# microphone_adapter_top.net
KiCad netlist of a schematic drawn in Altium Designer
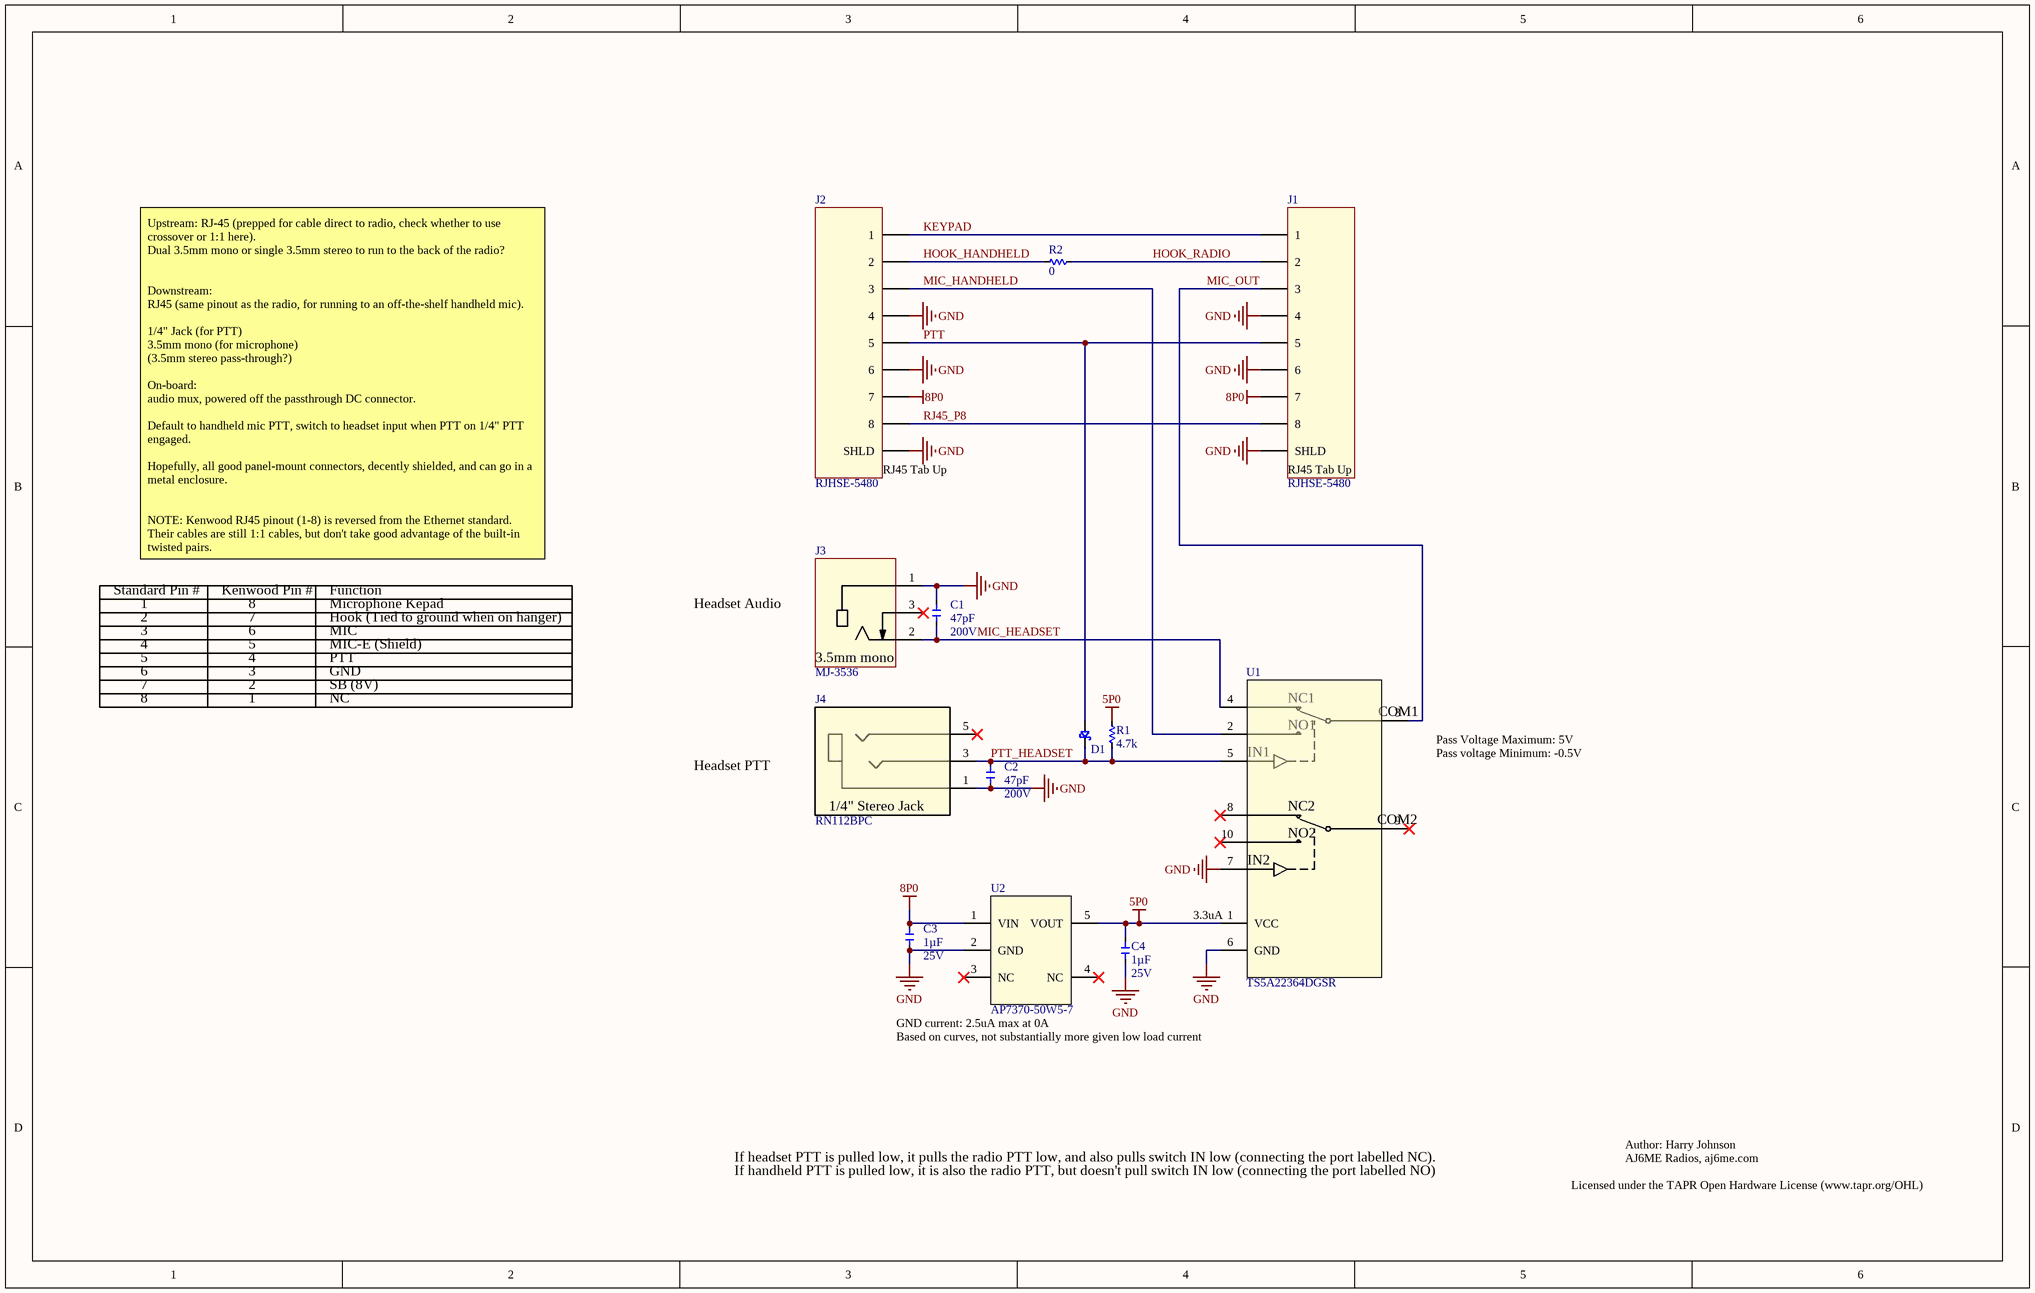
[diagram p0: microphone_adapter_top.SchDoc]

(export (version "E")
  (design (tool "Eeschema 10.0.6"))
  (components
    (comp (ref "C1")
      (value "GRM21A5C2D470JW01D")
      (footprint "C0805_1.30MM")
      (description "CAP CER 47PF 200V C0G/NP0 0805")
      (fields
        (field (name "CAPACITANCE") "47pF")
        (field (name "VOLTAGE - RATED") "200V")
        (field (name "DIGI-KEY PART NUMBER") "490-14653-1-ND")
        (field (name "MANUFACTURER") "Murata Electronics")
      )
      (libsource (lib "passives") (part "2pin_nonpolar_capacitor"))
    )
    (comp (ref "C2")
      (value "GRM21A5C2D470JW01D")
      (footprint "C0805_1.30MM")
      (description "CAP CER 47PF 200V C0G/NP0 0805")
      (fields
        (field (name "CAPACITANCE") "47pF")
        (field (name "VOLTAGE - RATED") "200V")
        (field (name "DIGI-KEY PART NUMBER") "490-14653-1-ND")
        (field (name "MANUFACTURER") "Murata Electronics")
      )
      (libsource (lib "passives") (part "2pin_nonpolar_capacitor"))
    )
    (comp (ref "C3")
      (value "GRM155C81E105ME11D")
      (footprint "C0402_0.55MM")
      (description "CAP CER 1UF 25V X6S 0402")
      (fields
        (field (name "CAPACITANCE") "1µF")
        (field (name "VOLTAGE - RATED") "25V")
        (field (name "DIGI-KEY PART NUMBER") "490-10015-1-ND")
        (field (name "MANUFACTURER") "Murata Electronics")
      )
      (libsource (lib "passives") (part "2pin_nonpolar_capacitor"))
    )
    (comp (ref "C4")
      (value "GRM155C81E105ME11D")
      (footprint "C0402_0.55MM")
      (description "CAP CER 1UF 25V X6S 0402")
      (fields
        (field (name "CAPACITANCE") "1µF")
        (field (name "VOLTAGE - RATED") "25V")
        (field (name "DIGI-KEY PART NUMBER") "490-10015-1-ND")
        (field (name "MANUFACTURER") "Murata Electronics")
      )
      (libsource (lib "passives") (part "2pin_nonpolar_capacitor"))
    )
    (comp (ref "D1")
      (value "BAT54XV2T1G")
      (footprint "SOD523_ONSEMI")
      (description "ON Semi BAT54XV2T1G; SMT Schottky Diode; 30V 200mA; 5ns; 2-Pin SOD-523")
      (fields (field (name "MANUFACTURER") "ON Semiconductor"))
      (libsource (lib "library") (part "DIODE_SCHOTTKY_30V_100MA_BAT54XV2T1G"))
    )
    (comp (ref "J1")
      (value "RJHSE-5480")
      (footprint "ETH_RJ45_RA_RJHSE-5480")
      (description "Conn RJ-45 F 8 POS 2.03mm Solder RA Thru-Hole 8 Terminal 1 Port Tray Cat 5")
      (fields (field (name "MANUFACTURER") "Amphenol"))
      (libsource (lib "library") (part "CONN_ETH_RJ45_RA_SHLD_RJHSE-5480_ALT"))
    )
    (comp (ref "J2")
      (value "RJHSE-5480")
      (footprint "ETH_RJ45_RA_RJHSE-5480")
      (description "Conn RJ-45 F 8 POS 2.03mm Solder RA Thru-Hole 8 Terminal 1 Port Tray Cat 5")
      (fields (field (name "MANUFACTURER") "Amphenol"))
      (libsource (lib "") (part "CONN_ETH_RJ45_RA_SHLD_RJHSE-5480_ALT_1"))
    )
    (comp (ref "J3")
      (value "MJ-3536")
      (footprint "AUD_CUI_MJ-3536")
      (description "CONN JACK MONO 3.5MM R/A")
      (fields (field (name "MANUFACTURER") "CUI"))
      (libsource (lib "library") (part "CONN_AUD_3.5_MM_MONO_MJ-3536"))
    )
    (comp (ref "J4")
      (value "RN112BPC")
      (footprint "AUD_SWITCHCRAFT_RN112BPC")
      (description "CONN JACK STEREO 0.25\" (6.35MM) R/A")
      (fields (field (name "MANUFACTURER") "Switchcraft"))
      (libsource (lib "library") (part "CONN_AUD_250_MIL_RN112BPC"))
    )
    (comp (ref "R1")
      (value "RC0402FR-074K7L")
      (footprint "R0402_0.40MM")
      (description "RES SMD 4.7K OHM 1% 1/16W 0402")
      (fields
        (field (name "RESISTANCE") "4.7k")
        (field (name "DIGI-KEY PART NUMBER") "311-4.7KLRCT-ND")
        (field (name "MANUFACTURER") "Yageo")
      )
      (libsource (lib "passives") (part "2pin_resistor"))
    )
    (comp (ref "R2")
      (value "RC0402JR-070RL")
      (footprint "R0402_0.40MM")
      (description "RES SMD 0 OHM JUMPER 1/16W 0402")
      (fields
        (field (name "RESISTANCE") "0")
        (field (name "DIGI-KEY PART NUMBER") "311-0.0JRCT-ND")
        (field (name "MANUFACTURER") "Yageo")
      )
      (libsource (lib "passives") (part "2pin_resistor"))
    )
    (comp (ref "U1")
      (value "TS5A22364DGSR")
      (footprint "TI_VSSOP_10_DGS0010A")
      (description "TEXAS INSTRUMENTS         TS5A22364DGSR.             ANALOG SWITCH, DUAL, SPDT, MSOP-10")
      (fields (field (name "MANUFACTURER") "Texas Instruments"))
      (libsource (lib "library") (part "IC_ANALOG_SWITCH_DUAL_SPDT_TS5A22364DGSR"))
    )
    (comp (ref "U2")
      (value "AP7370-50W5-7")
      (footprint "DIODES_INC_SOT25_5")
      (description "LDO Regulator Pos 5V 0.3A 5-Pin SOT-25 T/R")
      (fields (field (name "MANUFACTURER") "Diodes"))
      (libsource (lib "library") (part "LDO_5V_AP7370-50W5-7"))
    )
  )
  (nets
    (net (code "1") (name "/HOOK_HANDHELD") (class "Default")
      (node (ref "J2") (pin "2") (pinfunction "2_2") (pintype "passive"))
      (node (ref "R2") (pin "1") (pintype "passive"))
    )
    (net (code "2") (name "/HOOK_RADIO") (class "Default")
      (node (ref "J1") (pin "2") (pinfunction "2_2") (pintype "passive"))
      (node (ref "R2") (pin "2") (pintype "passive"))
    )
    (net (code "3") (name "/KEYPAD") (class "Default")
      (node (ref "J1") (pin "1") (pinfunction "1_1") (pintype "passive"))
      (node (ref "J2") (pin "1") (pinfunction "1_1") (pintype "passive"))
    )
    (net (code "4") (name "/MIC_HANDHELD") (class "Default")
      (node (ref "J2") (pin "3") (pinfunction "3_3") (pintype "passive"))
      (node (ref "U1") (pin "2") (pinfunction "NO1_2") (pintype "passive"))
    )
    (net (code "5") (name "/MIC_HEADSET") (class "Default")
      (node (ref "C1") (pin "2") (pintype "passive"))
      (node (ref "J3") (pin "2") (pinfunction "2_2") (pintype "passive"))
      (node (ref "U1") (pin "4") (pinfunction "NC1_4") (pintype "passive"))
    )
    (net (code "6") (name "/MIC_OUT") (class "Default")
      (node (ref "J1") (pin "3") (pinfunction "3_3") (pintype "passive"))
      (node (ref "U1") (pin "3") (pinfunction "COM1_3") (pintype "passive"))
    )
    (net (code "7") (name "/PTT") (class "Default")
      (node (ref "D1") (pin "2") (pintype "passive"))
      (node (ref "J1") (pin "5") (pinfunction "5_5") (pintype "passive"))
      (node (ref "J2") (pin "5") (pinfunction "5_5") (pintype "passive"))
    )
    (net (code "8") (name "/PTT_HEADSET") (class "Default")
      (node (ref "C2") (pin "1") (pintype "passive"))
      (node (ref "D1") (pin "1") (pintype "passive"))
      (node (ref "J4") (pin "3") (pinfunction "T_3") (pintype "passive"))
      (node (ref "R1") (pin "2") (pintype "passive"))
      (node (ref "U1") (pin "5") (pinfunction "IN1_5") (pintype "passive"))
    )
    (net (code "9") (name "/RJ45_P8") (class "Default")
      (node (ref "J1") (pin "8") (pinfunction "8_8") (pintype "passive"))
      (node (ref "J2") (pin "8") (pinfunction "8_8") (pintype "passive"))
    )
    (net (code "10") (name "5P0") (class "Default")
      (node (ref "C4") (pin "1") (pintype "passive"))
      (node (ref "R1") (pin "1") (pintype "passive"))
      (node (ref "U1") (pin "1") (pinfunction "VCC_1") (pintype "passive"))
      (node (ref "U2") (pin "5") (pinfunction "VOUT_5") (pintype "passive"))
    )
    (net (code "11") (name "8P0") (class "Default")
      (node (ref "C3") (pin "1") (pintype "passive"))
      (node (ref "J1") (pin "7") (pinfunction "7_7") (pintype "passive"))
      (node (ref "J2") (pin "7") (pinfunction "7_7") (pintype "passive"))
      (node (ref "U2") (pin "1") (pinfunction "VIN_1") (pintype "passive"))
    )
    (net (code "12") (name "GND") (class "Default")
      (node (ref "C1") (pin "1") (pintype "passive"))
      (node (ref "C2") (pin "2") (pintype "passive"))
      (node (ref "C3") (pin "2") (pintype "passive"))
      (node (ref "C4") (pin "2") (pintype "passive"))
      (node (ref "J1") (pin "4") (pinfunction "4_4") (pintype "passive"))
      (node (ref "J1") (pin "6") (pinfunction "6_6") (pintype "passive"))
      (node (ref "J1") (pin "SHLD") (pinfunction "SHLD_SHLD") (pintype "passive"))
      (node (ref "J2") (pin "4") (pinfunction "4_4") (pintype "passive"))
      (node (ref "J2") (pin "6") (pinfunction "6_6") (pintype "passive"))
      (node (ref "J2") (pin "SHLD") (pinfunction "SHLD_SHLD") (pintype "passive"))
      (node (ref "J3") (pin "1") (pinfunction "1_1") (pintype "passive"))
      (node (ref "J4") (pin "1") (pinfunction "S_1") (pintype "passive"))
      (node (ref "U1") (pin "6") (pinfunction "GND_6") (pintype "passive"))
      (node (ref "U1") (pin "7") (pinfunction "IN2_7") (pintype "passive"))
      (node (ref "U2") (pin "2") (pinfunction "GND_2") (pintype "passive"))
    )
    (net (code "13") (name "unconnected-(J3-Pad3)") (class "Default")
      (node (ref "J3") (pin "3") (pinfunction "3_3") (pintype "passive+no_connect"))
    )
    (net (code "14") (name "unconnected-(J4-R-Pad5)") (class "Default")
      (node (ref "J4") (pin "5") (pinfunction "R_5") (pintype "passive+no_connect"))
    )
    (net (code "15") (name "unconnected-(U1-COM2-Pad9)") (class "Default")
      (node (ref "U1") (pin "9") (pinfunction "COM2_9") (pintype "passive+no_connect"))
    )
    (net (code "16") (name "unconnected-(U1-NC2-Pad8)") (class "Default")
      (node (ref "U1") (pin "8") (pinfunction "NC2_8") (pintype "passive+no_connect"))
    )
    (net (code "17") (name "unconnected-(U1-NO2-Pad10)") (class "Default")
      (node (ref "U1") (pin "10") (pinfunction "NO2_10") (pintype "passive+no_connect"))
    )
    (net (code "18") (name "unconnected-(U2-NC-Pad3)") (class "Default")
      (node (ref "U2") (pin "3") (pinfunction "NC_3") (pintype "passive+no_connect"))
    )
    (net (code "19") (name "unconnected-(U2-NC-Pad4)") (class "Default")
      (node (ref "U2") (pin "4") (pinfunction "NC_4") (pintype "passive+no_connect"))
    )
  )
)
